# myBoardFPGA.net
KiCad netlist of a schematic drawn in EAGLE
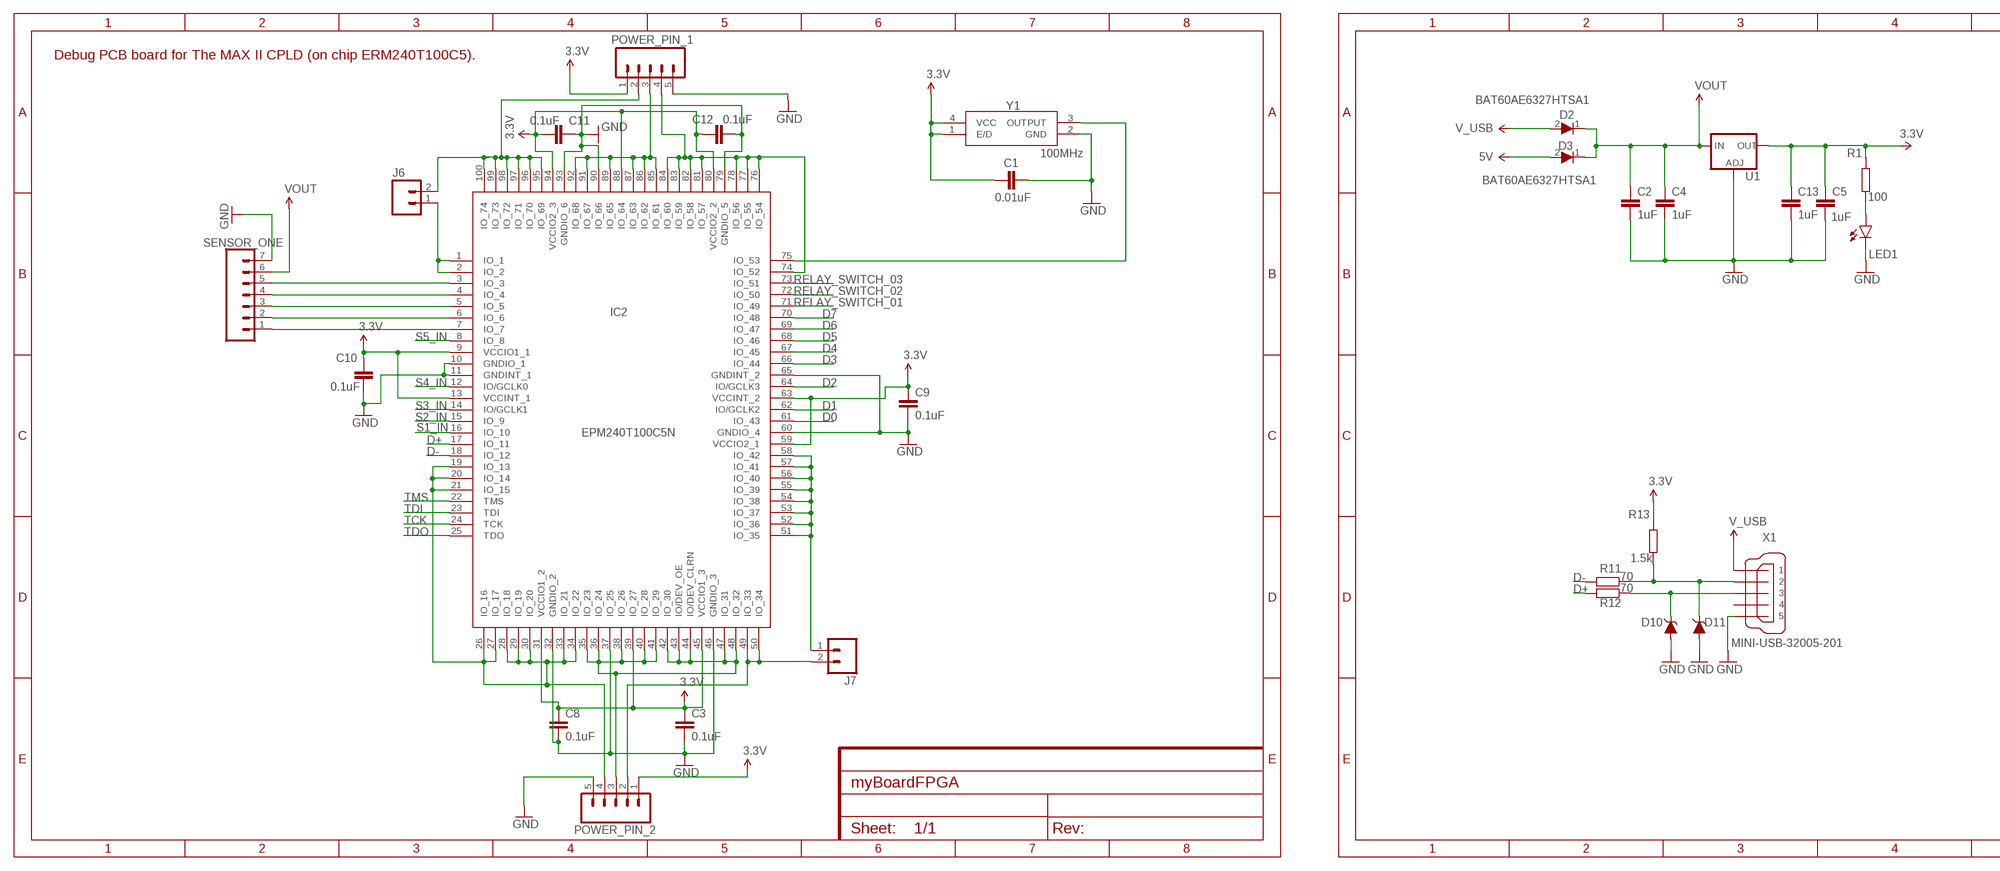
[diagram p0: schematic, sheet 1, part 1 of 2]
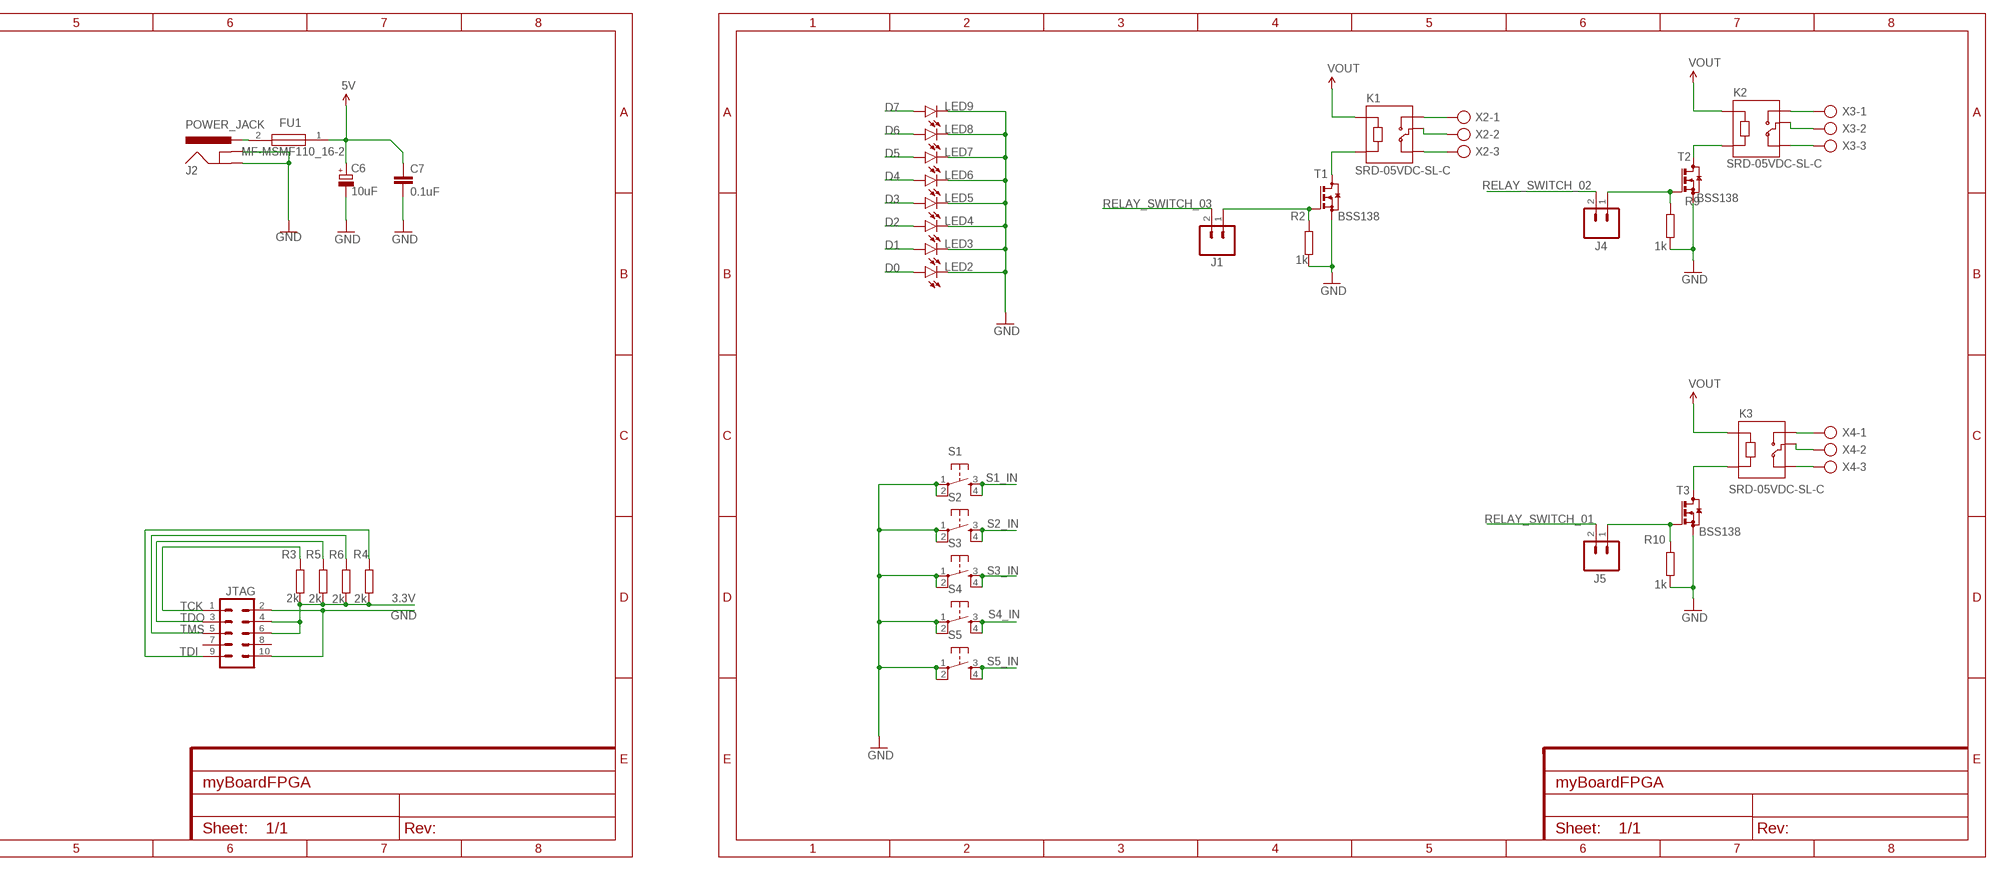
[diagram p1: schematic, sheet 1, part 2 of 2]

(export (version "E")
  (design (tool "Eeschema 10.0.6"))
  (components
    (comp (ref "C1")
      (value "0.01uF")
      (footprint "eagle-import:C1206")
      (libsource (lib "eagle-import") (part "C-EUC1206"))
    )
    (comp (ref "C2")
      (value "1uF")
      (footprint "eagle-import:C1206")
      (libsource (lib "eagle-import") (part "C-EUC1206"))
    )
    (comp (ref "C3")
      (value "0.1uF")
      (footprint "eagle-import:C1206")
      (libsource (lib "eagle-import") (part "C-EUC1206"))
    )
    (comp (ref "C4")
      (value "1uF")
      (footprint "eagle-import:C1206")
      (libsource (lib "eagle-import") (part "C-EUC1206"))
    )
    (comp (ref "C5")
      (value "1uF")
      (footprint "eagle-import:C1206")
      (libsource (lib "eagle-import") (part "C-EUC1206"))
    )
    (comp (ref "C6")
      (value "10uF")
      (footprint "eagle-import:E2-5")
      (libsource (lib "eagle-import") (part "CPOL-EUE2-5"))
    )
    (comp (ref "C7")
      (value "0.1uF")
      (footprint "eagle-import:C1206")
      (libsource (lib "eagle-import") (part "C-EUC1206"))
    )
    (comp (ref "C8")
      (value "0.1uF")
      (footprint "eagle-import:C1206")
      (libsource (lib "eagle-import") (part "C-EUC1206"))
    )
    (comp (ref "C9")
      (value "0.1uF")
      (footprint "eagle-import:C1206")
      (libsource (lib "eagle-import") (part "C-EUC1206"))
    )
    (comp (ref "C10")
      (value "0.1uF")
      (footprint "eagle-import:C1206")
      (libsource (lib "eagle-import") (part "C-EUC1206"))
    )
    (comp (ref "C11")
      (value "0.1uF")
      (footprint "eagle-import:C1206")
      (libsource (lib "eagle-import") (part "C-EUC1206"))
    )
    (comp (ref "C12")
      (value "0.1uF")
      (footprint "eagle-import:C1206")
      (libsource (lib "eagle-import") (part "C-EUC1206"))
    )
    (comp (ref "C13")
      (value "1uF")
      (footprint "eagle-import:C1206")
      (libsource (lib "eagle-import") (part "C-EUC1206"))
    )
    (comp (ref "D2")
      (value "BAT60AE6327HTSA1")
      (footprint "eagle-import:SOD2513X110N")
      (fields (field (name "MOUSER_PART_NUMBER") "726-BAT60AE6327HTSA1"))
      (libsource (lib "eagle-import") (part "BAT60AE6327HTSA1"))
    )
    (comp (ref "D3")
      (value "BAT60AE6327HTSA1")
      (footprint "eagle-import:SOD2513X110N")
      (fields (field (name "MOUSER_PART_NUMBER") "726-BAT60AE6327HTSA1"))
      (libsource (lib "eagle-import") (part "BAT60AE6327HTSA1"))
    )
    (comp (ref "D10")
      (value "3.3V")
      (footprint "eagle-import:BZV55C3V9TP")
      (libsource (lib "eagle-import") (part "DIODEZ"))
    )
    (comp (ref "D11")
      (value "3.6")
      (footprint "eagle-import:BZV55C3V9TP")
      (fields (field (name "SDA") "3.6V"))
      (libsource (lib "eagle-import") (part "DIODEZ"))
    )
    (comp (ref "FU1")
      (value "MF-MSMF110_16-2")
      (footprint "eagle-import:FUSC4632X85N")
      (fields
        (field (name "ARROW_PART_NUMBER") "MF-MSMF110/16-2")
        (field (name "MOUSER_PART_NUMBER") "652-MF-MSMF110/16-2")
      )
      (libsource (lib "eagle-import") (part "MF-MSMF110_16-2"))
    )
    (comp (ref "IC2")
      (value "EPM240T100C5N")
      (footprint "eagle-import:QFP50P1600X1600X120-100N")
      (fields (field (name "MOUSER_PART_NUMBER") "989-EPM240T100C5N"))
      (libsource (lib "eagle-import") (part "EPM240T100C5N"))
    )
    (comp (ref "J1")
      (value "M02LOCK")
      (footprint "eagle-import:1X02_LOCK")
      (libsource (lib "eagle-import") (part "M02LOCK"))
    )
    (comp (ref "J2")
      (value "POWER_JACK")
      (footprint "eagle-import:POWER_JACK_PTH")
      (libsource (lib "eagle-import") (part "POWER_JACK"))
    )
    (comp (ref "J4")
      (value "M02LOCK")
      (footprint "eagle-import:1X02_LOCK")
      (libsource (lib "eagle-import") (part "M02LOCK"))
    )
    (comp (ref "J5")
      (value "M02LOCK")
      (footprint "eagle-import:1X02_LOCK")
      (libsource (lib "eagle-import") (part "M02LOCK"))
    )
    (comp (ref "J6")
      (value "M02LOCK")
      (footprint "eagle-import:1X02_LOCK")
      (libsource (lib "eagle-import") (part "M02LOCK"))
    )
    (comp (ref "J7")
      (value "M02LOCK")
      (footprint "eagle-import:1X02_LOCK")
      (libsource (lib "eagle-import") (part "M02LOCK"))
    )
    (comp (ref "JTAG")
      (value "M05X2NO_SILK")
      (footprint "eagle-import:2X5_NOSILK")
      (libsource (lib "eagle-import") (part "M05X2NO_SILK"))
    )
    (comp (ref "K1")
      (value "SRD-05VDC-SL-C")
      (footprint "eagle-import:RELAY_SRD-05VDC-SL-C")
      (fields (field (name "MF") "Songle Relay"))
      (libsource (lib "eagle-import") (part "SRD-05VDC-SL-C"))
    )
    (comp (ref "K2")
      (value "SRD-05VDC-SL-C")
      (footprint "eagle-import:RELAY_SRD-05VDC-SL-C")
      (fields (field (name "MF") "Songle Relay"))
      (libsource (lib "eagle-import") (part "SRD-05VDC-SL-C"))
    )
    (comp (ref "K3")
      (value "SRD-05VDC-SL-C")
      (footprint "eagle-import:RELAY_SRD-05VDC-SL-C")
      (fields (field (name "MF") "Songle Relay"))
      (libsource (lib "eagle-import") (part "SRD-05VDC-SL-C"))
    )
    (comp (ref "LED1")
      (value "LEDSML0805")
      (footprint "eagle-import:SML0805")
      (libsource (lib "eagle-import") (part "LEDSML0805"))
    )
    (comp (ref "LED2")
      (value "LEDSMT1206")
      (footprint "eagle-import:1206")
      (libsource (lib "eagle-import") (part "LEDSMT1206"))
    )
    (comp (ref "LED3")
      (value "LEDSMT1206")
      (footprint "eagle-import:1206")
      (libsource (lib "eagle-import") (part "LEDSMT1206"))
    )
    (comp (ref "LED4")
      (value "LEDSMT1206")
      (footprint "eagle-import:1206")
      (libsource (lib "eagle-import") (part "LEDSMT1206"))
    )
    (comp (ref "LED5")
      (value "LEDSMT1206")
      (footprint "eagle-import:1206")
      (libsource (lib "eagle-import") (part "LEDSMT1206"))
    )
    (comp (ref "LED6")
      (value "LEDSMT1206")
      (footprint "eagle-import:1206")
      (libsource (lib "eagle-import") (part "LEDSMT1206"))
    )
    (comp (ref "LED7")
      (value "LEDSMT1206")
      (footprint "eagle-import:1206")
      (libsource (lib "eagle-import") (part "LEDSMT1206"))
    )
    (comp (ref "LED8")
      (value "LEDSMT1206")
      (footprint "eagle-import:1206")
      (libsource (lib "eagle-import") (part "LEDSMT1206"))
    )
    (comp (ref "LED9")
      (value "LEDSMT1206")
      (footprint "eagle-import:1206")
      (libsource (lib "eagle-import") (part "LEDSMT1206"))
    )
    (comp (ref "POWER_PIN_1")
      (value "M05LOCK")
      (footprint "eagle-import:1X05_LOCK")
      (libsource (lib "eagle-import") (part "M05LOCK"))
    )
    (comp (ref "POWER_PIN_2")
      (value "M05LOCK")
      (footprint "eagle-import:1X05_LOCK")
      (libsource (lib "eagle-import") (part "M05LOCK"))
    )
    (comp (ref "R1")
      (value "100")
      (footprint "eagle-import:R1206")
      (libsource (lib "eagle-import") (part "R-EU_R1206"))
    )
    (comp (ref "R2")
      (value "1k")
      (footprint "eagle-import:R1206")
      (libsource (lib "eagle-import") (part "R-EU_R1206"))
    )
    (comp (ref "R3")
      (value "2k")
      (footprint "eagle-import:R1206")
      (libsource (lib "eagle-import") (part "R-EU_R1206"))
    )
    (comp (ref "R4")
      (value "2k")
      (footprint "eagle-import:R1206")
      (libsource (lib "eagle-import") (part "R-EU_R1206"))
    )
    (comp (ref "R5")
      (value "2k")
      (footprint "eagle-import:R1206")
      (libsource (lib "eagle-import") (part "R-EU_R1206"))
    )
    (comp (ref "R6")
      (value "2k")
      (footprint "eagle-import:R1206")
      (libsource (lib "eagle-import") (part "R-EU_R1206"))
    )
    (comp (ref "R9")
      (value "1k")
      (footprint "eagle-import:R1206")
      (libsource (lib "eagle-import") (part "R-EU_R1206"))
    )
    (comp (ref "R10")
      (value "1k")
      (footprint "eagle-import:R1206")
      (libsource (lib "eagle-import") (part "R-EU_R1206"))
    )
    (comp (ref "R11")
      (value "70")
      (footprint "eagle-import:R1206")
      (libsource (lib "eagle-import") (part "R-EU_R1206"))
    )
    (comp (ref "R12")
      (value "70")
      (footprint "eagle-import:R1206")
      (libsource (lib "eagle-import") (part "R-EU_R1206"))
    )
    (comp (ref "R13")
      (value "1.5k")
      (footprint "eagle-import:R1206")
      (libsource (lib "eagle-import") (part "R-EU_R1206"))
    )
    (comp (ref "S1")
      (value "TAC_SWITCHPTH")
      (footprint "eagle-import:TACTILE-PTH")
      (libsource (lib "eagle-import") (part "TAC_SWITCHPTH"))
    )
    (comp (ref "S2")
      (value "TAC_SWITCHPTH")
      (footprint "eagle-import:TACTILE-PTH")
      (libsource (lib "eagle-import") (part "TAC_SWITCHPTH"))
    )
    (comp (ref "S3")
      (value "TAC_SWITCHPTH")
      (footprint "eagle-import:TACTILE-PTH")
      (libsource (lib "eagle-import") (part "TAC_SWITCHPTH"))
    )
    (comp (ref "S4")
      (value "TAC_SWITCHPTH")
      (footprint "eagle-import:TACTILE-PTH")
      (libsource (lib "eagle-import") (part "TAC_SWITCHPTH"))
    )
    (comp (ref "S5")
      (value "TAC_SWITCHPTH")
      (footprint "eagle-import:TACTILE-PTH")
      (libsource (lib "eagle-import") (part "TAC_SWITCHPTH"))
    )
    (comp (ref "SENSOR_ONE")
      (value "CONN_07")
      (footprint "eagle-import:1X07")
      (libsource (lib "eagle-import") (part "CONN_07"))
    )
    (comp (ref "T1")
      (value "BSS123")
      (footprint "eagle-import:SOT23")
      (fields (field (name "NEW") "BSS138"))
      (libsource (lib "eagle-import") (part "BSS123"))
    )
    (comp (ref "T2")
      (value "BSS123")
      (footprint "eagle-import:SOT23")
      (fields (field (name "BSS138") "BSS138"))
      (libsource (lib "eagle-import") (part "BSS123"))
    )
    (comp (ref "T3")
      (value "BSS123")
      (footprint "eagle-import:SOT23")
      (fields (field (name "NEW") "BSS138"))
      (libsource (lib "eagle-import") (part "BSS123"))
    )
    (comp (ref "U1")
      (value "V_REG_LM1117SOT223")
      (footprint "eagle-import:SOT223")
      (libsource (lib "eagle-import") (part "V_REG_LM1117SOT223"))
    )
    (comp (ref "X1")
      (value "MINI-USB-32005-201")
      (footprint "eagle-import:32005-201")
      (libsource (lib "eagle-import") (part "MINI-USB-32005-201"))
    )
    (comp (ref "X2")
      (value "AK300/3")
      (footprint "eagle-import:AK300_3")
      (libsource (lib "eagle-import") (part "AK300/3"))
    )
    (comp (ref "X3")
      (value "AK300/3")
      (footprint "eagle-import:AK300_3")
      (libsource (lib "eagle-import") (part "AK300/3"))
    )
    (comp (ref "X4")
      (value "AK300/3")
      (footprint "eagle-import:AK300_3")
      (libsource (lib "eagle-import") (part "AK300/3"))
    )
    (comp (ref "Y1")
      (value "100MHz")
      (footprint "eagle-import:CO4605100000TTR")
      (fields (field (name "MANUFACTURER_PART_NUMBER") "CO4605-100.000-T-TR") (field (name "NEW") "100MHz"))
      (libsource (lib "eagle-import") (part "CO4605-100.000-T-TR"))
    )
  )
  (nets
    (net (code "1") (name "/D+") (class "Default")
      (node (ref "IC2") (pin "17") (pinfunction "IO_11_17") (pintype "bidirectional"))
      (node (ref "R12") (pin "2") (pinfunction "2_2") (pintype "passive"))
    )
    (net (code "2") (name "/D-") (class "Default")
      (node (ref "IC2") (pin "18") (pinfunction "IO_12_18") (pintype "bidirectional"))
      (node (ref "R11") (pin "2") (pinfunction "2_2") (pintype "passive"))
    )
    (net (code "3") (name "/D0") (class "Default")
      (node (ref "IC2") (pin "61") (pinfunction "IO_43_61") (pintype "bidirectional"))
      (node (ref "LED2") (pin "A") (pinfunction "A_A") (pintype "passive"))
    )
    (net (code "4") (name "/D1") (class "Default")
      (node (ref "IC2") (pin "62") (pinfunction "IO/GCLK2_62") (pintype "bidirectional"))
      (node (ref "LED3") (pin "A") (pinfunction "A_A") (pintype "passive"))
    )
    (net (code "5") (name "/D2") (class "Default")
      (node (ref "IC2") (pin "64") (pinfunction "IO/GCLK3_64") (pintype "bidirectional"))
      (node (ref "LED4") (pin "A") (pinfunction "A_A") (pintype "passive"))
    )
    (net (code "6") (name "/D3") (class "Default")
      (node (ref "IC2") (pin "66") (pinfunction "IO_44_66") (pintype "bidirectional"))
      (node (ref "LED5") (pin "A") (pinfunction "A_A") (pintype "passive"))
    )
    (net (code "7") (name "/D4") (class "Default")
      (node (ref "IC2") (pin "67") (pinfunction "IO_45_67") (pintype "bidirectional"))
      (node (ref "LED6") (pin "A") (pinfunction "A_A") (pintype "passive"))
    )
    (net (code "8") (name "/D5") (class "Default")
      (node (ref "IC2") (pin "68") (pinfunction "IO_46_68") (pintype "bidirectional"))
      (node (ref "LED7") (pin "A") (pinfunction "A_A") (pintype "passive"))
    )
    (net (code "9") (name "/D6") (class "Default")
      (node (ref "IC2") (pin "69") (pinfunction "IO_47_69") (pintype "bidirectional"))
      (node (ref "LED8") (pin "A") (pinfunction "A_A") (pintype "passive"))
    )
    (net (code "10") (name "/D7") (class "Default")
      (node (ref "IC2") (pin "70") (pinfunction "IO_48_70") (pintype "bidirectional"))
      (node (ref "LED9") (pin "A") (pinfunction "A_A") (pintype "passive"))
    )
    (net (code "11") (name "/RELAY_SWITCH_01") (class "Default")
      (node (ref "IC2") (pin "71") (pinfunction "IO_49_71") (pintype "bidirectional"))
      (node (ref "J5") (pin "2") (pinfunction "2_2") (pintype "passive"))
    )
    (net (code "12") (name "/RELAY_SWITCH_02") (class "Default")
      (node (ref "IC2") (pin "72") (pinfunction "IO_50_72") (pintype "bidirectional"))
      (node (ref "J4") (pin "2") (pinfunction "2_2") (pintype "passive"))
    )
    (net (code "13") (name "/RELAY_SWITCH_03") (class "Default")
      (node (ref "IC2") (pin "73") (pinfunction "IO_51_73") (pintype "bidirectional"))
      (node (ref "J1") (pin "2") (pinfunction "2_2") (pintype "passive"))
    )
    (net (code "14") (name "/S1_IN") (class "Default")
      (node (ref "IC2") (pin "16") (pinfunction "IO_10_16") (pintype "bidirectional"))
      (node (ref "S1") (pin "3") (pinfunction "3_3") (pintype "passive"))
      (node (ref "S1") (pin "4") (pinfunction "4_4") (pintype "passive"))
    )
    (net (code "15") (name "/S2_IN") (class "Default")
      (node (ref "IC2") (pin "15") (pinfunction "IO_9_15") (pintype "bidirectional"))
      (node (ref "S2") (pin "3") (pinfunction "3_3") (pintype "passive"))
      (node (ref "S2") (pin "4") (pinfunction "4_4") (pintype "passive"))
    )
    (net (code "16") (name "/S3_IN") (class "Default")
      (node (ref "IC2") (pin "14") (pinfunction "IO/GCLK1_14") (pintype "bidirectional"))
      (node (ref "S3") (pin "3") (pinfunction "3_3") (pintype "passive"))
      (node (ref "S3") (pin "4") (pinfunction "4_4") (pintype "passive"))
    )
    (net (code "17") (name "/S4_IN") (class "Default")
      (node (ref "IC2") (pin "12") (pinfunction "IO/GCLK0_12") (pintype "bidirectional"))
      (node (ref "S4") (pin "3") (pinfunction "3_3") (pintype "passive"))
      (node (ref "S4") (pin "4") (pinfunction "4_4") (pintype "passive"))
    )
    (net (code "18") (name "/S5_IN") (class "Default")
      (node (ref "IC2") (pin "8") (pinfunction "IO_8_8") (pintype "bidirectional"))
      (node (ref "S5") (pin "3") (pinfunction "3_3") (pintype "passive"))
      (node (ref "S5") (pin "4") (pinfunction "4_4") (pintype "passive"))
    )
    (net (code "19") (name "/TCK") (class "Default")
      (node (ref "IC2") (pin "24") (pinfunction "TCK_24") (pintype "bidirectional"))
      (node (ref "JTAG") (pin "1") (pinfunction "1_1") (pintype "passive"))
      (node (ref "R3") (pin "2") (pinfunction "2_2") (pintype "passive"))
    )
    (net (code "20") (name "/TDI") (class "Default")
      (node (ref "IC2") (pin "23") (pinfunction "TDI_23") (pintype "bidirectional"))
      (node (ref "JTAG") (pin "9") (pinfunction "9_9") (pintype "passive"))
      (node (ref "R4") (pin "2") (pinfunction "2_2") (pintype "passive"))
    )
    (net (code "21") (name "/TDO") (class "Default")
      (node (ref "IC2") (pin "25") (pinfunction "TDO_25") (pintype "bidirectional"))
      (node (ref "JTAG") (pin "3") (pinfunction "3_3") (pintype "passive"))
      (node (ref "R5") (pin "2") (pinfunction "2_2") (pintype "passive"))
    )
    (net (code "22") (name "/TMS") (class "Default")
      (node (ref "IC2") (pin "22") (pinfunction "TMS_22") (pintype "bidirectional"))
      (node (ref "JTAG") (pin "5") (pinfunction "5_5") (pintype "passive"))
      (node (ref "R6") (pin "2") (pinfunction "2_2") (pintype "passive"))
    )
    (net (code "23") (name "3.3V") (class "Default")
      (node (ref "C1") (pin "1") (pinfunction "1_1") (pintype "passive"))
      (node (ref "C10") (pin "1") (pinfunction "1_1") (pintype "passive"))
      (node (ref "C11") (pin "2") (pinfunction "2_2") (pintype "passive"))
      (node (ref "C12") (pin "1") (pinfunction "1_1") (pintype "passive"))
      (node (ref "C13") (pin "1") (pinfunction "1_1") (pintype "passive"))
      (node (ref "C3") (pin "1") (pinfunction "1_1") (pintype "passive"))
      (node (ref "C5") (pin "1") (pinfunction "1_1") (pintype "passive"))
      (node (ref "C8") (pin "1") (pinfunction "1_1") (pintype "passive"))
      (node (ref "C9") (pin "1") (pinfunction "1_1") (pintype "passive"))
      (node (ref "IC2") (pin "13") (pinfunction "VCCINT_1_13") (pintype "bidirectional"))
      (node (ref "IC2") (pin "31") (pinfunction "VCCIO1_2_31") (pintype "bidirectional"))
      (node (ref "IC2") (pin "39") (pinfunction "IO_27_39") (pintype "bidirectional"))
      (node (ref "IC2") (pin "45") (pinfunction "VCCIO1_3_45") (pintype "bidirectional"))
      (node (ref "IC2") (pin "59") (pinfunction "VCCIO2_1_59") (pintype "bidirectional"))
      (node (ref "IC2") (pin "63") (pinfunction "VCCINT_2_63") (pintype "bidirectional"))
      (node (ref "IC2") (pin "80") (pinfunction "VCCIO2_2_80") (pintype "bidirectional"))
      (node (ref "IC2") (pin "88") (pinfunction "IO_64_88") (pintype "bidirectional"))
      (node (ref "IC2") (pin "9") (pinfunction "VCCIO1_1_9") (pintype "bidirectional"))
      (node (ref "IC2") (pin "94") (pinfunction "VCCIO2_3_94") (pintype "bidirectional"))
      (node (ref "JTAG") (pin "4") (pinfunction "4_4") (pintype "passive"))
      (node (ref "JTAG") (pin "6") (pinfunction "6_6") (pintype "passive"))
      (node (ref "POWER_PIN_1") (pin "1") (pinfunction "1_1") (pintype "passive"))
      (node (ref "POWER_PIN_2") (pin "1") (pinfunction "1_1") (pintype "passive"))
      (node (ref "R1") (pin "2") (pinfunction "2_2") (pintype "passive"))
      (node (ref "R13") (pin "2") (pinfunction "2_2") (pintype "passive"))
      (node (ref "R3") (pin "1") (pinfunction "1_1") (pintype "passive"))
      (node (ref "R4") (pin "1") (pinfunction "1_1") (pintype "passive"))
      (node (ref "R5") (pin "1") (pinfunction "1_1") (pintype "passive"))
      (node (ref "R6") (pin "1") (pinfunction "1_1") (pintype "passive"))
      (node (ref "U1") (pin "2") (pinfunction "OUT_2") (pintype "output"))
      (node (ref "U1") (pin "4") (pinfunction "OUT_4") (pintype "output"))
      (node (ref "Y1") (pin "1") (pinfunction "E/D_1") (pintype "bidirectional"))
      (node (ref "Y1") (pin "4") (pinfunction "VCC_4") (pintype "bidirectional"))
    )
    (net (code "24") (name "5V") (class "Default")
      (node (ref "C6") (pin "+") (pinfunction "+_+") (pintype "passive"))
      (node (ref "C7") (pin "1") (pinfunction "1_1") (pintype "passive"))
      (node (ref "D3") (pin "2") (pinfunction "A_2") (pintype "bidirectional"))
      (node (ref "FU1") (pin "1") (pinfunction "1_1") (pintype "bidirectional"))
    )
    (net (code "25") (name "GND") (class "Default")
      (node (ref "C1") (pin "2") (pinfunction "2_2") (pintype "passive"))
      (node (ref "C10") (pin "2") (pinfunction "2_2") (pintype "passive"))
      (node (ref "C11") (pin "1") (pinfunction "1_1") (pintype "passive"))
      (node (ref "C12") (pin "2") (pinfunction "2_2") (pintype "passive"))
      (node (ref "C13") (pin "2") (pinfunction "2_2") (pintype "passive"))
      (node (ref "C2") (pin "2") (pinfunction "2_2") (pintype "passive"))
      (node (ref "C3") (pin "2") (pinfunction "2_2") (pintype "passive"))
      (node (ref "C4") (pin "2") (pinfunction "2_2") (pintype "passive"))
      (node (ref "C5") (pin "2") (pinfunction "2_2") (pintype "passive"))
      (node (ref "C6") (pin "-") (pinfunction "-_-") (pintype "passive"))
      (node (ref "C7") (pin "2") (pinfunction "2_2") (pintype "passive"))
      (node (ref "C8") (pin "2") (pinfunction "2_2") (pintype "passive"))
      (node (ref "C9") (pin "2") (pinfunction "2_2") (pintype "passive"))
      (node (ref "D10") (pin "1") (pinfunction "A_1") (pintype "passive"))
      (node (ref "D11") (pin "1") (pinfunction "A_1") (pintype "passive"))
      (node (ref "IC2") (pin "10") (pinfunction "GNDIO_1_10") (pintype "bidirectional"))
      (node (ref "IC2") (pin "11") (pinfunction "GNDINT_1_11") (pintype "bidirectional"))
      (node (ref "IC2") (pin "32") (pinfunction "GNDIO_2_32") (pintype "bidirectional"))
      (node (ref "IC2") (pin "37") (pinfunction "IO_25_37") (pintype "bidirectional"))
      (node (ref "IC2") (pin "46") (pinfunction "GNDIO_3_46") (pintype "bidirectional"))
      (node (ref "IC2") (pin "60") (pinfunction "GNDIO_4_60") (pintype "bidirectional"))
      (node (ref "IC2") (pin "65") (pinfunction "GNDINT_2_65") (pintype "bidirectional"))
      (node (ref "IC2") (pin "79") (pinfunction "GNDIO_5_79") (pintype "bidirectional"))
      (node (ref "IC2") (pin "90") (pinfunction "IO_66_90") (pintype "bidirectional"))
      (node (ref "IC2") (pin "93") (pinfunction "GNDIO_6_93") (pintype "bidirectional"))
      (node (ref "J2") (pin "GND") (pinfunction "GND_GND") (pintype "bidirectional"))
      (node (ref "J2") (pin "GNDBREAK") (pinfunction "GNDBREAK_GNDBREAK") (pintype "bidirectional"))
      (node (ref "JTAG") (pin "10") (pinfunction "10_10") (pintype "passive"))
      (node (ref "JTAG") (pin "2") (pinfunction "2_2") (pintype "passive"))
      (node (ref "LED1") (pin "C") (pinfunction "C_C") (pintype "passive"))
      (node (ref "LED2") (pin "C") (pinfunction "C_C") (pintype "passive"))
      (node (ref "LED3") (pin "C") (pinfunction "C_C") (pintype "passive"))
      (node (ref "LED4") (pin "C") (pinfunction "C_C") (pintype "passive"))
      (node (ref "LED5") (pin "C") (pinfunction "C_C") (pintype "passive"))
      (node (ref "LED6") (pin "C") (pinfunction "C_C") (pintype "passive"))
      (node (ref "LED7") (pin "C") (pinfunction "C_C") (pintype "passive"))
      (node (ref "LED8") (pin "C") (pinfunction "C_C") (pintype "passive"))
      (node (ref "LED9") (pin "C") (pinfunction "C_C") (pintype "passive"))
      (node (ref "POWER_PIN_1") (pin "5") (pinfunction "5_5") (pintype "passive"))
      (node (ref "POWER_PIN_2") (pin "5") (pinfunction "5_5") (pintype "passive"))
      (node (ref "R10") (pin "1") (pinfunction "1_1") (pintype "passive"))
      (node (ref "R2") (pin "1") (pinfunction "1_1") (pintype "passive"))
      (node (ref "R9") (pin "1") (pinfunction "1_1") (pintype "passive"))
      (node (ref "S1") (pin "1") (pinfunction "1_1") (pintype "passive"))
      (node (ref "S1") (pin "2") (pinfunction "2_2") (pintype "passive"))
      (node (ref "S2") (pin "1") (pinfunction "1_1") (pintype "passive"))
      (node (ref "S2") (pin "2") (pinfunction "2_2") (pintype "passive"))
      (node (ref "S3") (pin "1") (pinfunction "1_1") (pintype "passive"))
      (node (ref "S3") (pin "2") (pinfunction "2_2") (pintype "passive"))
      (node (ref "S4") (pin "1") (pinfunction "1_1") (pintype "passive"))
      (node (ref "S4") (pin "2") (pinfunction "2_2") (pintype "passive"))
      (node (ref "S5") (pin "1") (pinfunction "1_1") (pintype "passive"))
      (node (ref "S5") (pin "2") (pinfunction "2_2") (pintype "passive"))
      (node (ref "SENSOR_ONE") (pin "7") (pinfunction "7_7") (pintype "passive"))
      (node (ref "T1") (pin "2") (pinfunction "S_2") (pintype "passive"))
      (node (ref "T2") (pin "2") (pinfunction "S_2") (pintype "passive"))
      (node (ref "T3") (pin "2") (pinfunction "S_2") (pintype "passive"))
      (node (ref "U1") (pin "1") (pinfunction "ADJ_1") (pintype "input"))
      (node (ref "X1") (pin "5") (pinfunction "5_5") (pintype "passive"))
      (node (ref "Y1") (pin "2") (pinfunction "GND_2") (pintype "bidirectional"))
    )
    (net (code "26") (name "Net-(D10-C)") (class "Default")
      (node (ref "D10") (pin "2") (pinfunction "C_2") (pintype "passive"))
      (node (ref "R12") (pin "1") (pinfunction "1_1") (pintype "passive"))
      (node (ref "X1") (pin "3") (pinfunction "3_3") (pintype "passive"))
    )
    (net (code "27") (name "Net-(D11-C)") (class "Default")
      (node (ref "D11") (pin "2") (pinfunction "C_2") (pintype "passive"))
      (node (ref "R11") (pin "1") (pinfunction "1_1") (pintype "passive"))
      (node (ref "R13") (pin "1") (pinfunction "1_1") (pintype "passive"))
      (node (ref "X1") (pin "2") (pinfunction "2_2") (pintype "passive"))
    )
    (net (code "28") (name "Net-(FU1-Pad2)") (class "Default")
      (node (ref "FU1") (pin "2") (pinfunction "2_2") (pintype "bidirectional"))
      (node (ref "J2") (pin "PWR") (pinfunction "PWR_PWR") (pintype "bidirectional"))
    )
    (net (code "29") (name "Net-(IC2-IO_1)") (class "Default")
      (node (ref "IC2") (pin "1") (pinfunction "IO_1_1") (pintype "bidirectional"))
      (node (ref "IC2") (pin "2") (pinfunction "IO_2_2") (pintype "bidirectional"))
      (node (ref "J6") (pin "1") (pinfunction "1_1") (pintype "passive"))
    )
    (net (code "30") (name "Net-(IC2-IO_3)") (class "Default")
      (node (ref "IC2") (pin "3") (pinfunction "IO_3_3") (pintype "bidirectional"))
      (node (ref "SENSOR_ONE") (pin "5") (pinfunction "5_5") (pintype "passive"))
    )
    (net (code "31") (name "Net-(IC2-IO_4)") (class "Default")
      (node (ref "IC2") (pin "4") (pinfunction "IO_4_4") (pintype "bidirectional"))
      (node (ref "SENSOR_ONE") (pin "4") (pinfunction "4_4") (pintype "passive"))
    )
    (net (code "32") (name "Net-(IC2-IO_5)") (class "Default")
      (node (ref "IC2") (pin "5") (pinfunction "IO_5_5") (pintype "bidirectional"))
      (node (ref "SENSOR_ONE") (pin "3") (pinfunction "3_3") (pintype "passive"))
    )
    (net (code "33") (name "Net-(IC2-IO_6)") (class "Default")
      (node (ref "IC2") (pin "6") (pinfunction "IO_6_6") (pintype "bidirectional"))
      (node (ref "SENSOR_ONE") (pin "2") (pinfunction "2_2") (pintype "passive"))
    )
    (net (code "34") (name "Net-(IC2-IO_7)") (class "Default")
      (node (ref "IC2") (pin "7") (pinfunction "IO_7_7") (pintype "bidirectional"))
      (node (ref "SENSOR_ONE") (pin "1") (pinfunction "1_1") (pintype "passive"))
    )
    (net (code "35") (name "Net-(IC2-IO_13)") (class "Default")
      (node (ref "IC2") (pin "19") (pinfunction "IO_13_19") (pintype "bidirectional"))
      (node (ref "IC2") (pin "20") (pinfunction "IO_14_20") (pintype "bidirectional"))
      (node (ref "IC2") (pin "21") (pinfunction "IO_15_21") (pintype "bidirectional"))
      (node (ref "IC2") (pin "26") (pinfunction "IO_16_26") (pintype "bidirectional"))
      (node (ref "IC2") (pin "27") (pinfunction "IO_17_27") (pintype "bidirectional"))
      (node (ref "IC2") (pin "28") (pinfunction "IO_18_28") (pintype "bidirectional"))
      (node (ref "IC2") (pin "29") (pinfunction "IO_19_29") (pintype "bidirectional"))
      (node (ref "IC2") (pin "30") (pinfunction "IO_20_30") (pintype "bidirectional"))
      (node (ref "IC2") (pin "33") (pinfunction "IO_21_33") (pintype "bidirectional"))
      (node (ref "IC2") (pin "34") (pinfunction "IO_22_34") (pintype "bidirectional"))
      (node (ref "POWER_PIN_2") (pin "4") (pinfunction "4_4") (pintype "passive"))
    )
    (net (code "36") (name "Net-(IC2-IO_23)") (class "Default")
      (node (ref "IC2") (pin "35") (pinfunction "IO_23_35") (pintype "bidirectional"))
      (node (ref "IC2") (pin "36") (pinfunction "IO_24_36") (pintype "bidirectional"))
      (node (ref "IC2") (pin "38") (pinfunction "IO_26_38") (pintype "bidirectional"))
      (node (ref "IC2") (pin "40") (pinfunction "IO_28_40") (pintype "bidirectional"))
      (node (ref "IC2") (pin "41") (pinfunction "IO_29_41") (pintype "bidirectional"))
      (node (ref "IC2") (pin "42") (pinfunction "IO_30_42") (pintype "bidirectional"))
      (node (ref "IC2") (pin "43") (pinfunction "IO/DEV_OE_43") (pintype "bidirectional"))
      (node (ref "IC2") (pin "44") (pinfunction "IO/DEV_CLRN_44") (pintype "bidirectional"))
      (node (ref "IC2") (pin "47") (pinfunction "IO_31_47") (pintype "bidirectional"))
      (node (ref "IC2") (pin "48") (pinfunction "IO_32_48") (pintype "bidirectional"))
      (node (ref "POWER_PIN_2") (pin "3") (pinfunction "3_3") (pintype "passive"))
    )
    (net (code "37") (name "Net-(IC2-IO_33)") (class "Default")
      (node (ref "IC2") (pin "49") (pinfunction "IO_33_49") (pintype "bidirectional"))
      (node (ref "IC2") (pin "50") (pinfunction "IO_34_50") (pintype "bidirectional"))
      (node (ref "J7") (pin "2") (pinfunction "2_2") (pintype "passive"))
      (node (ref "POWER_PIN_2") (pin "2") (pinfunction "2_2") (pintype "passive"))
    )
    (net (code "38") (name "Net-(IC2-IO_35)") (class "Default")
      (node (ref "IC2") (pin "51") (pinfunction "IO_35_51") (pintype "bidirectional"))
      (node (ref "IC2") (pin "52") (pinfunction "IO_36_52") (pintype "bidirectional"))
      (node (ref "IC2") (pin "53") (pinfunction "IO_37_53") (pintype "bidirectional"))
      (node (ref "IC2") (pin "54") (pinfunction "IO_38_54") (pintype "bidirectional"))
      (node (ref "IC2") (pin "55") (pinfunction "IO_39_55") (pintype "bidirectional"))
      (node (ref "IC2") (pin "56") (pinfunction "IO_40_56") (pintype "bidirectional"))
      (node (ref "IC2") (pin "57") (pinfunction "IO_41_57") (pintype "bidirectional"))
      (node (ref "IC2") (pin "58") (pinfunction "IO_42_58") (pintype "bidirectional"))
      (node (ref "J7") (pin "1") (pinfunction "1_1") (pintype "passive"))
    )
    (net (code "39") (name "Net-(IC2-IO_52)") (class "Default")
      (node (ref "IC2") (pin "74") (pinfunction "IO_52_74") (pintype "bidirectional"))
      (node (ref "IC2") (pin "76") (pinfunction "IO_54_76") (pintype "bidirectional"))
      (node (ref "IC2") (pin "77") (pinfunction "IO_55_77") (pintype "bidirectional"))
      (node (ref "IC2") (pin "78") (pinfunction "IO_56_78") (pintype "bidirectional"))
      (node (ref "IC2") (pin "81") (pinfunction "IO_57_81") (pintype "bidirectional"))
      (node (ref "IC2") (pin "82") (pinfunction "IO_58_82") (pintype "bidirectional"))
      (node (ref "IC2") (pin "83") (pinfunction "IO_59_83") (pintype "bidirectional"))
      (node (ref "IC2") (pin "84") (pinfunction "IO_60_84") (pintype "bidirectional"))
      (node (ref "POWER_PIN_1") (pin "4") (pinfunction "4_4") (pintype "passive"))
    )
    (net (code "40") (name "Net-(IC2-IO_53)") (class "Default")
      (node (ref "IC2") (pin "75") (pinfunction "IO_53_75") (pintype "bidirectional"))
      (node (ref "Y1") (pin "3") (pinfunction "OUTPUT_3") (pintype "bidirectional"))
    )
    (net (code "41") (name "Net-(IC2-IO_61)") (class "Default")
      (node (ref "IC2") (pin "85") (pinfunction "IO_61_85") (pintype "bidirectional"))
      (node (ref "IC2") (pin "86") (pinfunction "IO_62_86") (pintype "bidirectional"))
      (node (ref "IC2") (pin "87") (pinfunction "IO_63_87") (pintype "bidirectional"))
      (node (ref "IC2") (pin "89") (pinfunction "IO_65_89") (pintype "bidirectional"))
      (node (ref "IC2") (pin "91") (pinfunction "IO_67_91") (pintype "bidirectional"))
      (node (ref "IC2") (pin "92") (pinfunction "IO_68_92") (pintype "bidirectional"))
      (node (ref "POWER_PIN_1") (pin "3") (pinfunction "3_3") (pintype "passive"))
    )
    (net (code "42") (name "Net-(IC2-IO_69)") (class "Default")
      (node (ref "IC2") (pin "100") (pinfunction "IO_74_100") (pintype "bidirectional"))
      (node (ref "IC2") (pin "95") (pinfunction "IO_69_95") (pintype "bidirectional"))
      (node (ref "IC2") (pin "96") (pinfunction "IO_70_96") (pintype "bidirectional"))
      (node (ref "IC2") (pin "97") (pinfunction "IO_71_97") (pintype "bidirectional"))
      (node (ref "IC2") (pin "98") (pinfunction "IO_72_98") (pintype "bidirectional"))
      (node (ref "IC2") (pin "99") (pinfunction "IO_73_99") (pintype "bidirectional"))
      (node (ref "J6") (pin "2") (pinfunction "2_2") (pintype "passive"))
      (node (ref "POWER_PIN_1") (pin "2") (pinfunction "2_2") (pintype "passive"))
    )
    (net (code "43") (name "Net-(LED1-PadA)") (class "Default")
      (node (ref "LED1") (pin "A") (pinfunction "A_A") (pintype "passive"))
      (node (ref "R1") (pin "1") (pinfunction "1_1") (pintype "passive"))
    )
    (net (code "44") (name "Net-(T1-D)") (class "Default")
      (node (ref "K1") (pin "A2") (pinfunction "A2_A2") (pintype "passive"))
      (node (ref "T1") (pin "3") (pinfunction "D_3") (pintype "passive"))
    )
    (net (code "45") (name "Net-(T1-G)") (class "Default")
      (node (ref "J1") (pin "1") (pinfunction "1_1") (pintype "passive"))
      (node (ref "R2") (pin "2") (pinfunction "2_2") (pintype "passive"))
      (node (ref "T1") (pin "1") (pinfunction "G_1") (pintype "passive"))
    )
    (net (code "46") (name "Net-(T2-D)") (class "Default")
      (node (ref "K2") (pin "A2") (pinfunction "A2_A2") (pintype "passive"))
      (node (ref "T2") (pin "3") (pinfunction "D_3") (pintype "passive"))
    )
    (net (code "47") (name "Net-(T2-G)") (class "Default")
      (node (ref "J4") (pin "1") (pinfunction "1_1") (pintype "passive"))
      (node (ref "R9") (pin "2") (pinfunction "2_2") (pintype "passive"))
      (node (ref "T2") (pin "1") (pinfunction "G_1") (pintype "passive"))
    )
    (net (code "48") (name "Net-(T3-D)") (class "Default")
      (node (ref "K3") (pin "A2") (pinfunction "A2_A2") (pintype "passive"))
      (node (ref "T3") (pin "3") (pinfunction "D_3") (pintype "passive"))
    )
    (net (code "49") (name "Net-(T3-G)") (class "Default")
      (node (ref "J5") (pin "1") (pinfunction "1_1") (pintype "passive"))
      (node (ref "R10") (pin "2") (pinfunction "2_2") (pintype "passive"))
      (node (ref "T3") (pin "1") (pinfunction "G_1") (pintype "passive"))
    )
    (net (code "50") (name "Net-(X2A-KL)") (class "Default")
      (node (ref "K1") (pin "NO") (pinfunction "NO_NO") (pintype "passive"))
      (node (ref "X2") (pin "1") (pinfunction "KL_1") (pintype "passive"))
    )
    (net (code "51") (name "Net-(X2B-KL)") (class "Default")
      (node (ref "K1") (pin "COM") (pinfunction "COM_COM") (pintype "passive"))
      (node (ref "X2") (pin "2") (pinfunction "KL_2") (pintype "passive"))
    )
    (net (code "52") (name "Net-(X2C-KL)") (class "Default")
      (node (ref "K1") (pin "NC") (pinfunction "NC_NC") (pintype "passive"))
      (node (ref "X2") (pin "3") (pinfunction "KL_3") (pintype "passive"))
    )
    (net (code "53") (name "Net-(X3A-KL)") (class "Default")
      (node (ref "K2") (pin "NO") (pinfunction "NO_NO") (pintype "passive"))
      (node (ref "X3") (pin "1") (pinfunction "KL_1") (pintype "passive"))
    )
    (net (code "54") (name "Net-(X3B-KL)") (class "Default")
      (node (ref "K2") (pin "COM") (pinfunction "COM_COM") (pintype "passive"))
      (node (ref "X3") (pin "2") (pinfunction "KL_2") (pintype "passive"))
    )
    (net (code "55") (name "Net-(X3C-KL)") (class "Default")
      (node (ref "K2") (pin "NC") (pinfunction "NC_NC") (pintype "passive"))
      (node (ref "X3") (pin "3") (pinfunction "KL_3") (pintype "passive"))
    )
    (net (code "56") (name "Net-(X4A-KL)") (class "Default")
      (node (ref "K3") (pin "NO") (pinfunction "NO_NO") (pintype "passive"))
      (node (ref "X4") (pin "1") (pinfunction "KL_1") (pintype "passive"))
    )
    (net (code "57") (name "Net-(X4B-KL)") (class "Default")
      (node (ref "K3") (pin "COM") (pinfunction "COM_COM") (pintype "passive"))
      (node (ref "X4") (pin "2") (pinfunction "KL_2") (pintype "passive"))
    )
    (net (code "58") (name "Net-(X4C-KL)") (class "Default")
      (node (ref "K3") (pin "NC") (pinfunction "NC_NC") (pintype "passive"))
      (node (ref "X4") (pin "3") (pinfunction "KL_3") (pintype "passive"))
    )
    (net (code "59") (name "VOUT") (class "Default")
      (node (ref "C2") (pin "1") (pinfunction "1_1") (pintype "passive"))
      (node (ref "C4") (pin "1") (pinfunction "1_1") (pintype "passive"))
      (node (ref "D2") (pin "1") (pinfunction "K_1") (pintype "bidirectional"))
      (node (ref "D3") (pin "1") (pinfunction "K_1") (pintype "bidirectional"))
      (node (ref "K1") (pin "A1") (pinfunction "A1_A1") (pintype "passive"))
      (node (ref "K2") (pin "A1") (pinfunction "A1_A1") (pintype "passive"))
      (node (ref "K3") (pin "A1") (pinfunction "A1_A1") (pintype "passive"))
      (node (ref "SENSOR_ONE") (pin "6") (pinfunction "6_6") (pintype "passive"))
      (node (ref "U1") (pin "3") (pinfunction "IN_3") (pintype "input"))
    )
    (net (code "60") (name "V_USB") (class "Default")
      (node (ref "D2") (pin "2") (pinfunction "A_2") (pintype "bidirectional"))
      (node (ref "X1") (pin "1") (pinfunction "1_1") (pintype "passive"))
    )
    (net (code "61") (name "unconnected-(JTAG-Pad7)") (class "Default")
      (node (ref "JTAG") (pin "7") (pinfunction "7_7") (pintype "passive"))
    )
    (net (code "62") (name "unconnected-(JTAG-Pad8)") (class "Default")
      (node (ref "JTAG") (pin "8") (pinfunction "8_8") (pintype "passive"))
    )
    (net (code "63") (name "unconnected-(X1-Pad4)") (class "Default")
      (node (ref "X1") (pin "4") (pinfunction "4_4") (pintype "passive"))
    )
  )
)
